# Potencia.net
KiCad netlist of a schematic drawn in Altium Designer
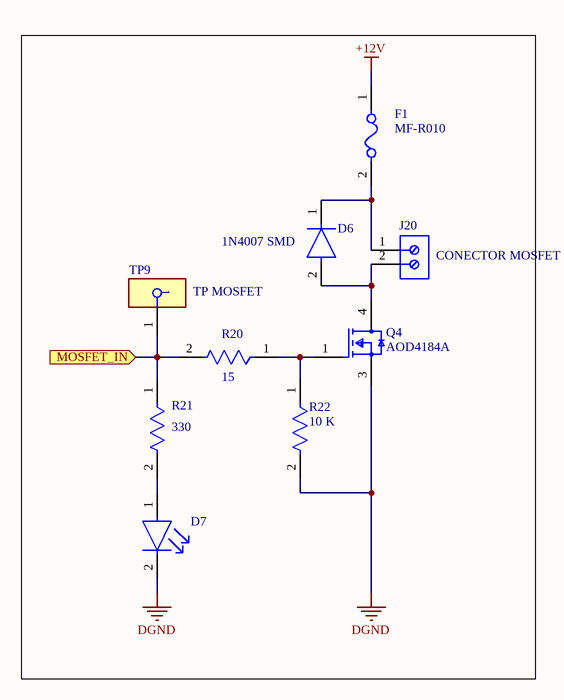
[diagram p0: Potencia.SchDoc]

(export (version "E")
  (design (tool "Eeschema 10.0.6"))
  (components
    (comp (ref "D6")
      (value "1N4007 SMD")
      (footprint "FP-1N4007_SMD-IPC_C")
      (description "DIODE 1N4148 THT / Proteccion Mosfet")
      (libsource (lib "Altium Content Vault") (part "d7152d700b627762746794eb795d46e"))
    )
    (comp (ref "D7")
      (value "SM0805YCL")
      (footprint "FP-SM0805YCL-MFG")
      (description "LED SMD 0805 / Mosfet status")
      (libsource (lib "Altium Content Vault") (part "ab1c01a81903e929fc6c44469aada92"))
    )
    (comp (ref "F1")
      (value "MF-R010")
      (footprint "FP-MF-R010-MFG")
      (description "PTC RESET FUSE 60V 100MA RADIAL")
      (fields
        (field (name "MANUFACTURER") "Bourns Inc.")
        (field (name "OCTOPART") "https://octopart.com/mf-r010-bourns-5791")
      )
      (libsource (lib "Altium Content Vault") (part "5bcf9b9f640e542cf0359d10258e979"))
    )
    (comp (ref "J20")
      (value "CONECTOR MOSFET")
      (footprint "691102710002")
      (description "TERMINAL BLOCK 2 POS / Salida Mosfet")
      (fields (field (name "VOLTAGE") "300V"))
      (libsource (lib "Altium Content Vault") (part "TBL - 1R - 02P - Screw"))
    )
    (comp (ref "Q4")
      (value "AOD4184A")
      (footprint "FP-TO252-MFG")
      (description "MOSFET N AOD4148A TO252")
      (libsource (lib "Altium Content Vault") (part "eaf820099600a16e7148a0c70285cb7"))
    )
    (comp (ref "R20")
      (value "15")
      (footprint "FP-RN73R2A-IPC_A")
      (description "RES 15R 5% 0805")
      (libsource (lib "Altium Content Vault") (part "1029c3af85768c4190bb7ad29bc67b5"))
    )
    (comp (ref "R21")
      (value "330")
      (footprint "FP-RN73R2A-IPC_A")
      (description "RES 330R 5% 0805")
      (libsource (lib "Altium Content Vault") (part "1029c3af85768c4190bb7ad29bc67b5"))
    )
    (comp (ref "R22")
      (value "10 K")
      (footprint "FP-RN73R2A-IPC_A")
      (description "RES 10K 5% 0805")
      (libsource (lib "Altium Content Vault") (part "1029c3af85768c4190bb7ad29bc67b5"))
    )
    (comp (ref "TP9")
      (value "TP MOSFET")
      (footprint "FP-5004-MFG")
      (description "PC TEST POINT MINIATURE YELLOW")
      (fields (field (name "MANUFACTURER") "Keystone") (field (name "MANUFACTURER PART NUMBER") "5004"))
      (libsource (lib "Altium Content Vault") (part "98815daf2f2c152b0c43f5ab9800df6"))
    )
  )
  (nets
    (net (code "1") (name "+12V") (class "Default")
      (node (ref "F1") (pin "1") (pinfunction "1_1") (pintype "passive"))
    )
    (net (code "2") (name "/MOSFET_IN") (class "Default")
      (node (ref "R20") (pin "2") (pinfunction "2_2") (pintype "passive"))
      (node (ref "R21") (pin "1") (pinfunction "1_1") (pintype "passive"))
      (node (ref "TP9") (pin "1") (pinfunction "1_1") (pintype "passive"))
    )
    (net (code "3") (name "DGND") (class "Default")
      (node (ref "D7") (pin "2") (pinfunction "C_2") (pintype "passive"))
      (node (ref "Q4") (pin "3") (pinfunction "S_3") (pintype "passive"))
      (node (ref "R22") (pin "2") (pinfunction "2_2") (pintype "passive"))
    )
    (net (code "4") (name "Net-(D6-A)") (class "Default")
      (node (ref "D6") (pin "2") (pinfunction "A_2") (pintype "passive"))
      (node (ref "J20") (pin "2") (pinfunction "2_2") (pintype "passive"))
      (node (ref "Q4") (pin "4") (pinfunction "D_4") (pintype "passive"))
    )
    (net (code "5") (name "Net-(D6-C)") (class "Default")
      (node (ref "D6") (pin "1") (pinfunction "C_1") (pintype "passive"))
      (node (ref "F1") (pin "2") (pinfunction "2_2") (pintype "passive"))
      (node (ref "J20") (pin "1") (pinfunction "1_1") (pintype "passive"))
    )
    (net (code "6") (name "Net-(D7-A)") (class "Default")
      (node (ref "D7") (pin "1") (pinfunction "A_1") (pintype "passive"))
      (node (ref "R21") (pin "2") (pinfunction "2_2") (pintype "passive"))
    )
    (net (code "7") (name "Net-(Q4-G)") (class "Default")
      (node (ref "Q4") (pin "1") (pinfunction "G_1") (pintype "passive"))
      (node (ref "R20") (pin "1") (pinfunction "1_1") (pintype "passive"))
      (node (ref "R22") (pin "1") (pinfunction "1_1") (pintype "passive"))
    )
  )
)
